# ProjectorAdapter.net
KiCad netlist of a schematic drawn in EAGLE
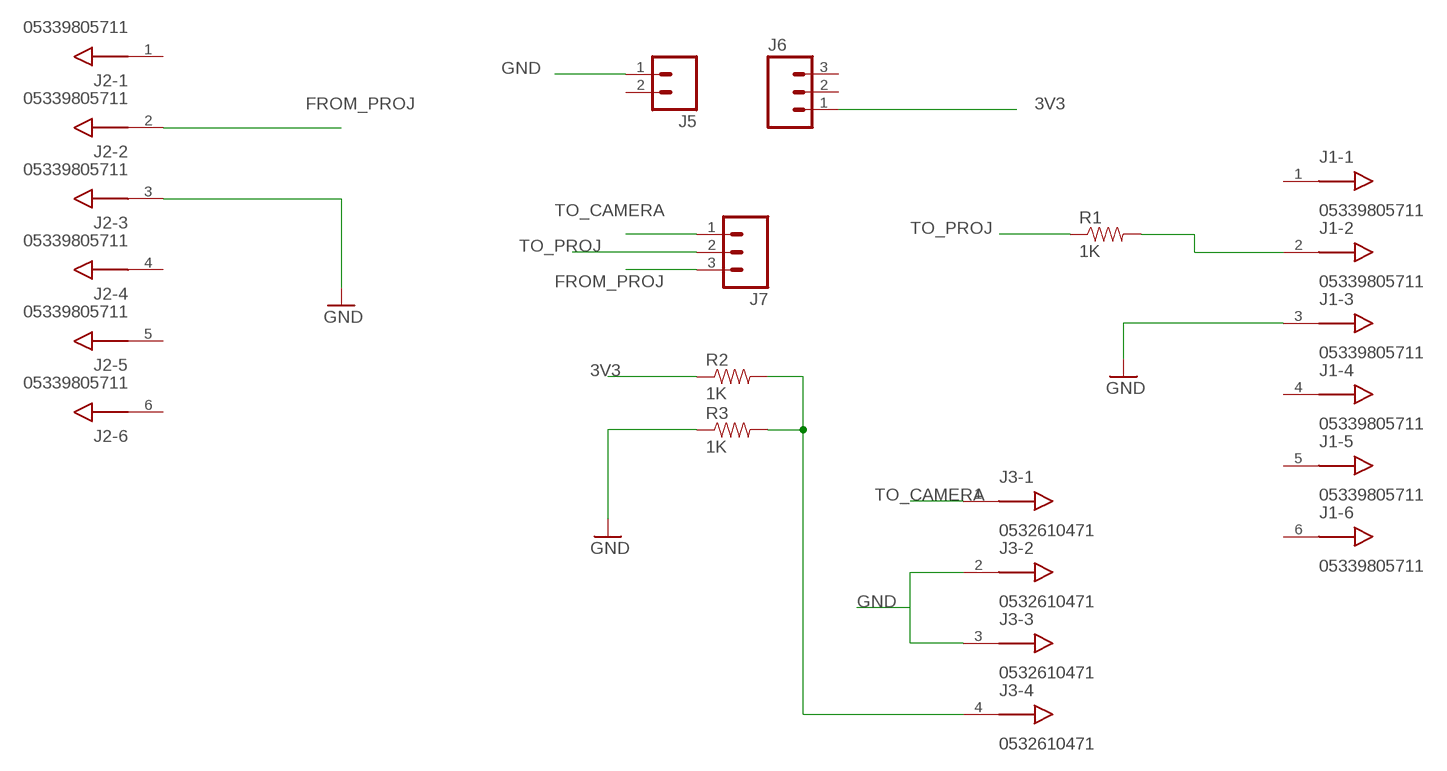
[diagram p0: schematic, sheet 1]

(export (version "E")
  (design (tool "Eeschema 10.0.6"))
  (components
    (comp (ref "J1")
      (value "05339805711")
      (footprint "eagle-import:PICOBLADE53398-0671")
      (fields (field (name "MANUFACTURER") "Molex Inc"))
      (libsource (lib "eagle-import") (part "05339805711"))
    )
    (comp (ref "J2")
      (value "05339805711")
      (footprint "eagle-import:PICOBLADE53398-0671")
      (fields (field (name "MANUFACTURER") "Molex Inc"))
      (libsource (lib "eagle-import") (part "05339805711"))
    )
    (comp (ref "J3")
      (value "0532610471")
      (footprint "eagle-import:PICOBLADE53261-0471")
      (fields (field (name "MANUFACTURER") "Molex Inc") (field (name "PART_NUMBER") "0533980371"))
      (libsource (lib "eagle-import") (part "0532610471"))
    )
    (comp (ref "J5")
      (value "M02PTH")
      (footprint "eagle-import:1X02")
      (libsource (lib "eagle-import") (part "M02PTH"))
    )
    (comp (ref "J6")
      (value "M03PTH")
      (footprint "eagle-import:1X03")
      (libsource (lib "eagle-import") (part "M03PTH"))
    )
    (comp (ref "J7")
      (value "M03PTH")
      (footprint "eagle-import:1X03")
      (libsource (lib "eagle-import") (part "M03PTH"))
    )
    (comp (ref "R1")
      (value "1K")
      (footprint "eagle-import:0603-RES")
      (libsource (lib "eagle-import") (part "RESISTOR0603-RES"))
    )
    (comp (ref "R2")
      (value "1K")
      (footprint "eagle-import:0603-RES")
      (libsource (lib "eagle-import") (part "RESISTOR0603-RES"))
    )
    (comp (ref "R3")
      (value "1K")
      (footprint "eagle-import:0603-RES")
      (libsource (lib "eagle-import") (part "RESISTOR0603-RES"))
    )
  )
  (nets
    (net (code "1") (name "/3V3") (class "Default")
      (node (ref "J6") (pin "1") (pinfunction "1_1") (pintype "passive"))
      (node (ref "R2") (pin "1") (pinfunction "1_1") (pintype "passive"))
    )
    (net (code "2") (name "/FROM_PROJ") (class "Default")
      (node (ref "J2") (pin "2") (pinfunction "P$1_2") (pintype "bidirectional"))
      (node (ref "J7") (pin "3") (pinfunction "3_3") (pintype "passive"))
    )
    (net (code "3") (name "/TO_CAMERA") (class "Default")
      (node (ref "J3") (pin "1") (pinfunction "P$1_1") (pintype "bidirectional"))
      (node (ref "J7") (pin "1") (pinfunction "1_1") (pintype "passive"))
    )
    (net (code "4") (name "/TO_PROJ") (class "Default")
      (node (ref "J7") (pin "2") (pinfunction "2_2") (pintype "passive"))
      (node (ref "R1") (pin "1") (pinfunction "1_1") (pintype "passive"))
    )
    (net (code "5") (name "GND") (class "Default")
      (node (ref "J1") (pin "3") (pinfunction "P$1_3") (pintype "bidirectional"))
      (node (ref "J2") (pin "3") (pinfunction "P$1_3") (pintype "bidirectional"))
      (node (ref "J3") (pin "2") (pinfunction "P$1_2") (pintype "bidirectional"))
      (node (ref "J3") (pin "3") (pinfunction "P$1_3") (pintype "bidirectional"))
      (node (ref "J5") (pin "1") (pinfunction "1_1") (pintype "passive"))
      (node (ref "R3") (pin "1") (pinfunction "1_1") (pintype "passive"))
    )
    (net (code "6") (name "Net-(J1B-P$1)") (class "Default")
      (node (ref "J1") (pin "2") (pinfunction "P$1_2") (pintype "bidirectional"))
      (node (ref "R1") (pin "2") (pinfunction "2_2") (pintype "passive"))
    )
    (net (code "7") (name "Net-(J3D-P$1)") (class "Default")
      (node (ref "J3") (pin "4") (pinfunction "P$1_4") (pintype "bidirectional"))
      (node (ref "R2") (pin "2") (pinfunction "2_2") (pintype "passive"))
      (node (ref "R3") (pin "2") (pinfunction "2_2") (pintype "passive"))
    )
    (net (code "8") (name "unconnected-(J1A-P$1-Pad1)") (class "Default")
      (node (ref "J1") (pin "1") (pinfunction "P$1_1") (pintype "bidirectional"))
    )
    (net (code "9") (name "unconnected-(J1D-P$1-Pad4)") (class "Default")
      (node (ref "J1") (pin "4") (pinfunction "P$1_4") (pintype "bidirectional"))
    )
    (net (code "10") (name "unconnected-(J1E-P$1-Pad5)") (class "Default")
      (node (ref "J1") (pin "5") (pinfunction "P$1_5") (pintype "bidirectional"))
    )
    (net (code "11") (name "unconnected-(J1F-P$1-Pad6)") (class "Default")
      (node (ref "J1") (pin "6") (pinfunction "P$1_6") (pintype "bidirectional"))
    )
    (net (code "12") (name "unconnected-(J2A-P$1-Pad1)") (class "Default")
      (node (ref "J2") (pin "1") (pinfunction "P$1_1") (pintype "bidirectional"))
    )
    (net (code "13") (name "unconnected-(J2D-P$1-Pad4)") (class "Default")
      (node (ref "J2") (pin "4") (pinfunction "P$1_4") (pintype "bidirectional"))
    )
    (net (code "14") (name "unconnected-(J2E-P$1-Pad5)") (class "Default")
      (node (ref "J2") (pin "5") (pinfunction "P$1_5") (pintype "bidirectional"))
    )
    (net (code "15") (name "unconnected-(J2F-P$1-Pad6)") (class "Default")
      (node (ref "J2") (pin "6") (pinfunction "P$1_6") (pintype "bidirectional"))
    )
    (net (code "16") (name "unconnected-(J5-Pad2)") (class "Default")
      (node (ref "J5") (pin "2") (pinfunction "2_2") (pintype "passive"))
    )
    (net (code "17") (name "unconnected-(J6-Pad2)") (class "Default")
      (node (ref "J6") (pin "2") (pinfunction "2_2") (pintype "passive"))
    )
    (net (code "18") (name "unconnected-(J6-Pad3)") (class "Default")
      (node (ref "J6") (pin "3") (pinfunction "3_3") (pintype "passive"))
    )
  )
)
